# LPS_Breakout.net
KiCad netlist of a schematic drawn in EAGLE
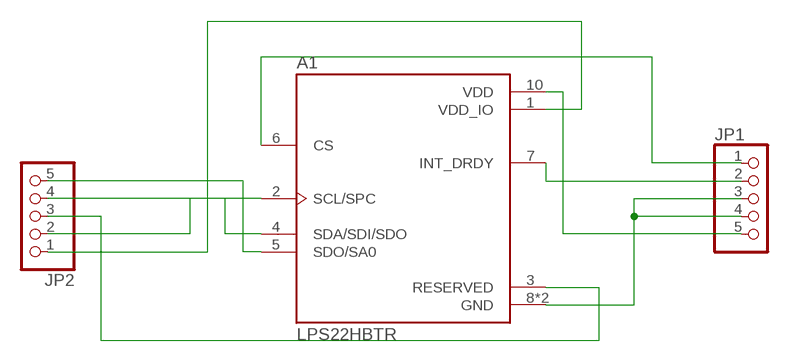
[diagram p0: schematic, sheet 1]

(export (version "E")
  (design (tool "Eeschema 10.0.6"))
  (components
    (comp (ref "A1")
      (value "LPS22HBTR")
      (footprint "eagle-import:PQFN50P200X200X80-10N")
      (fields (field (name "DIGI-KEY_PART_NUMBER") "497-16265-1-ND") (field (name "MF") "STMicroelectronics"))
      (libsource (lib "eagle-import") (part "LPS22HBTR"))
    )
    (comp (ref "JP1")
      (value "PINHD-1X5")
      (footprint "eagle-import:1X05")
      (libsource (lib "eagle-import") (part "PINHD-1X5"))
    )
    (comp (ref "JP2")
      (value "PINHD-1X5")
      (footprint "eagle-import:1X05")
      (libsource (lib "eagle-import") (part "PINHD-1X5"))
    )
  )
  (nets
    (net (code "1") (name "Net-(A1-CS)") (class "Default")
      (node (ref "A1") (pin "6") (pinfunction "CS_6") (pintype "input"))
      (node (ref "JP1") (pin "1") (pinfunction "1_1") (pintype "passive"))
    )
    (net (code "2") (name "Net-(A1-GND-Pad8)") (class "Default")
      (node (ref "A1") (pin "8") (pinfunction "GND_8") (pintype "power_in"))
      (node (ref "A1") (pin "9") (pinfunction "GND_9") (pintype "power_in"))
      (node (ref "JP1") (pin "3") (pinfunction "3_3") (pintype "passive"))
      (node (ref "JP1") (pin "4") (pinfunction "4_4") (pintype "passive"))
    )
    (net (code "3") (name "Net-(A1-INT_DRDY)") (class "Default")
      (node (ref "A1") (pin "7") (pinfunction "INT_DRDY_7") (pintype "output"))
      (node (ref "JP1") (pin "2") (pinfunction "2_2") (pintype "passive"))
    )
    (net (code "4") (name "Net-(A1-RESERVED)") (class "Default")
      (node (ref "A1") (pin "3") (pinfunction "RESERVED_3") (pintype "passive"))
      (node (ref "JP2") (pin "3") (pinfunction "3_3") (pintype "passive"))
    )
    (net (code "5") (name "Net-(A1-SCL{slash}SPC)") (class "Default")
      (node (ref "A1") (pin "2") (pinfunction "SCL/SPC_2") (pintype "input"))
      (node (ref "JP2") (pin "2") (pinfunction "2_2") (pintype "passive"))
    )
    (net (code "6") (name "Net-(A1-SDA{slash}SDI{slash}SDO)") (class "Default")
      (node (ref "A1") (pin "4") (pinfunction "SDA/SDI/SDO_4") (pintype "bidirectional"))
      (node (ref "JP2") (pin "4") (pinfunction "4_4") (pintype "passive"))
    )
    (net (code "7") (name "Net-(A1-SDO{slash}SA0)") (class "Default")
      (node (ref "A1") (pin "5") (pinfunction "SDO/SA0_5") (pintype "bidirectional"))
      (node (ref "JP2") (pin "5") (pinfunction "5_5") (pintype "passive"))
    )
    (net (code "8") (name "Net-(A1-VDD)") (class "Default")
      (node (ref "A1") (pin "10") (pinfunction "VDD_10") (pintype "power_in"))
      (node (ref "JP1") (pin "5") (pinfunction "5_5") (pintype "passive"))
    )
    (net (code "9") (name "Net-(A1-VDD_IO)") (class "Default")
      (node (ref "A1") (pin "1") (pinfunction "VDD_IO_1") (pintype "power_in"))
      (node (ref "JP2") (pin "1") (pinfunction "1_1") (pintype "passive"))
    )
  )
)
